# tweeq-Stamp_I2C_Temp_TMP102.net
KiCad netlist of a schematic drawn in EAGLE
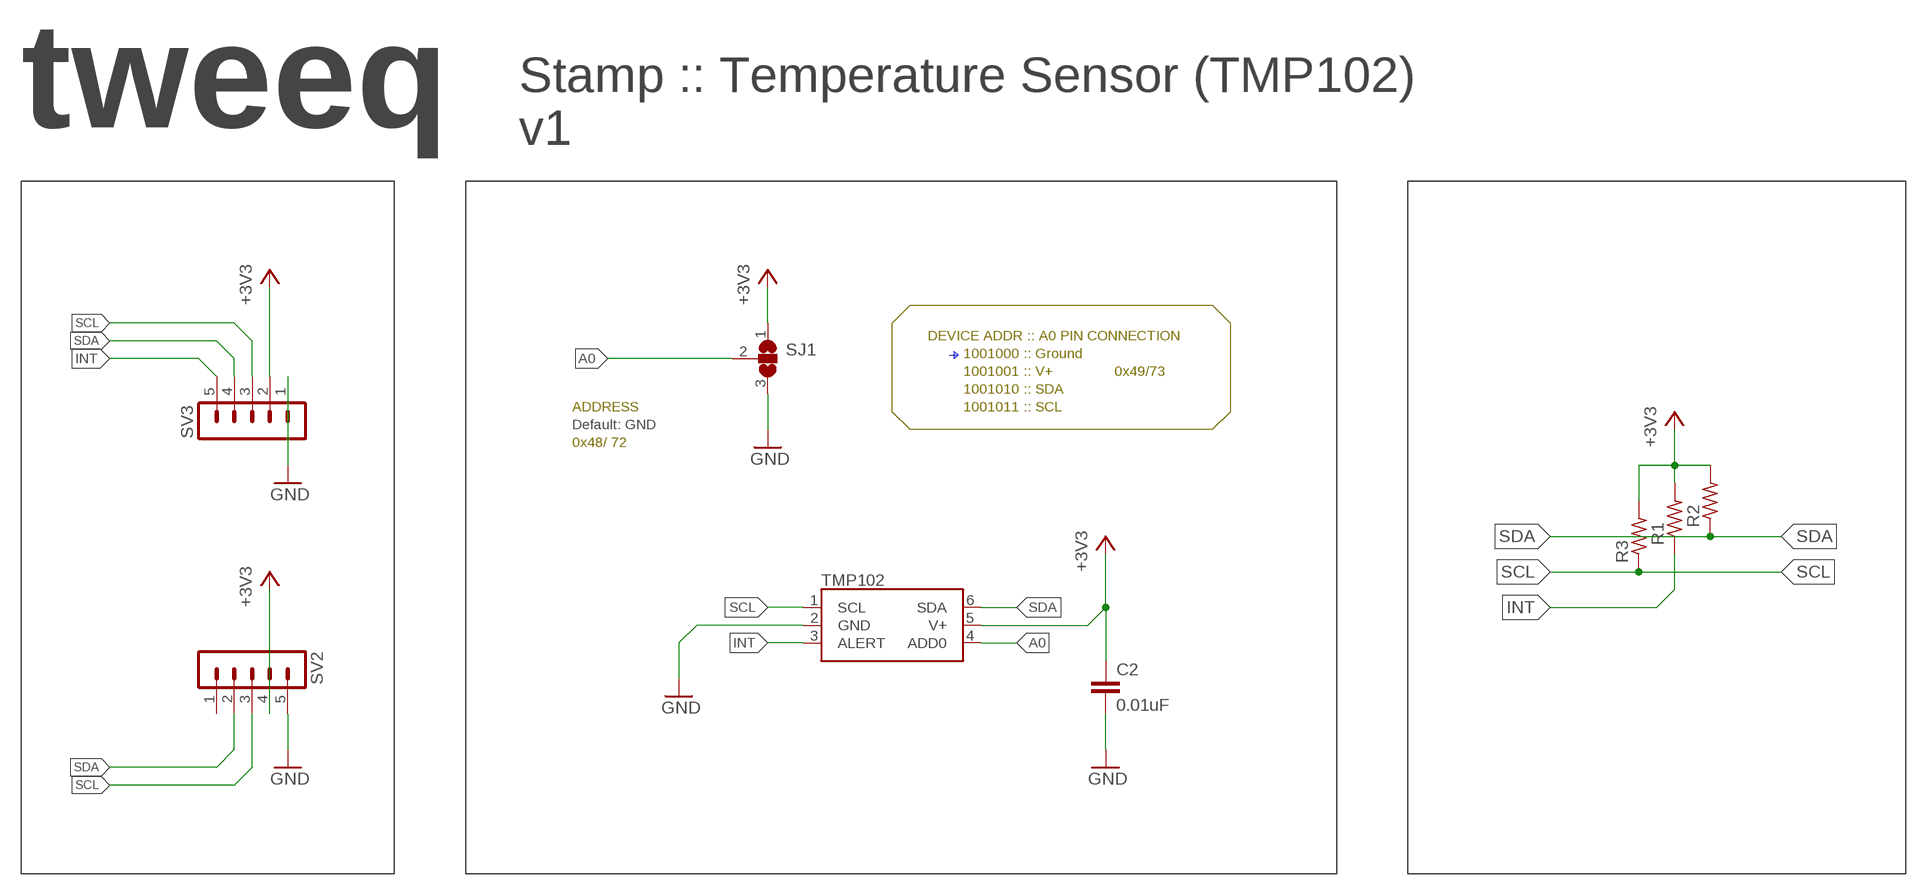
[diagram p0: schematic, sheet 1]

(export (version "E")
  (design (tool "Eeschema 10.0.6"))
  (components
    (comp (ref "C2")
      (value "0.01uF")
      (footprint "eagle-import:C0402K")
      (libsource (lib "eagle-import") (part "C-EUC0402K"))
    )
    (comp (ref "R1")
      (value "R-US_R0402")
      (footprint "eagle-import:R0402")
      (libsource (lib "eagle-import") (part "R-US_R0402"))
    )
    (comp (ref "R2")
      (value "R-US_R0402")
      (footprint "eagle-import:R0402")
      (libsource (lib "eagle-import") (part "R-US_R0402"))
    )
    (comp (ref "R3")
      (value "R-US_R0402")
      (footprint "eagle-import:R0402")
      (libsource (lib "eagle-import") (part "R-US_R0402"))
    )
    (comp (ref "SJ1")
      (value "JUMPER_SJ2WS")
      (footprint "eagle-import:JUMPER_SJ_S")
      (libsource (lib "eagle-import") (part "JUMPER_SJ2WS"))
    )
    (comp (ref "SV2")
      (value "M05-1STAMP")
      (footprint "eagle-import:1X05-1.5MM-STAMP")
      (libsource (lib "eagle-import") (part "M05-1STAMP"))
    )
    (comp (ref "SV3")
      (value "M05-1STAMP")
      (footprint "eagle-import:1X05-1.5MM-STAMP")
      (libsource (lib "eagle-import") (part "M05-1STAMP"))
    )
    (comp (ref "TMP102")
      (value "TMP102/SOT563")
      (footprint "eagle-import:SOT563")
      (libsource (lib "eagle-import") (part "TMP102/SOT563"))
    )
  )
  (nets
    (net (code "1") (name "+3V3") (class "Default")
      (node (ref "C2") (pin "1") (pinfunction "1_1") (pintype "passive"))
      (node (ref "R1") (pin "2") (pinfunction "2_2") (pintype "passive"))
      (node (ref "R2") (pin "2") (pinfunction "2_2") (pintype "passive"))
      (node (ref "R3") (pin "2") (pinfunction "2_2") (pintype "passive"))
      (node (ref "SJ1") (pin "1") (pinfunction "1_1") (pintype "passive"))
      (node (ref "SV2") (pin "4") (pinfunction "4_4") (pintype "passive"))
      (node (ref "SV3") (pin "2") (pinfunction "2_2") (pintype "passive"))
      (node (ref "TMP102") (pin "5") (pinfunction "V+_5") (pintype "bidirectional"))
    )
    (net (code "2") (name "A0") (class "Default")
      (node (ref "SJ1") (pin "2") (pinfunction "2_2") (pintype "passive"))
      (node (ref "TMP102") (pin "4") (pinfunction "ADD0_4") (pintype "bidirectional"))
    )
    (net (code "3") (name "GND") (class "Default")
      (node (ref "C2") (pin "2") (pinfunction "2_2") (pintype "passive"))
      (node (ref "SJ1") (pin "3") (pinfunction "3_3") (pintype "passive"))
      (node (ref "SV2") (pin "5") (pinfunction "5_5") (pintype "passive"))
      (node (ref "SV3") (pin "1") (pinfunction "1_1") (pintype "passive"))
      (node (ref "TMP102") (pin "2") (pinfunction "GND_2") (pintype "bidirectional"))
    )
    (net (code "4") (name "INT") (class "Default")
      (node (ref "R1") (pin "1") (pinfunction "1_1") (pintype "passive"))
      (node (ref "SV3") (pin "5") (pinfunction "5_5") (pintype "passive"))
      (node (ref "TMP102") (pin "3") (pinfunction "ALERT_3") (pintype "bidirectional"))
    )
    (net (code "5") (name "SCL") (class "Default")
      (node (ref "R3") (pin "1") (pinfunction "1_1") (pintype "passive"))
      (node (ref "SV2") (pin "3") (pinfunction "3_3") (pintype "passive"))
      (node (ref "SV3") (pin "3") (pinfunction "3_3") (pintype "passive"))
      (node (ref "TMP102") (pin "1") (pinfunction "SCL_1") (pintype "bidirectional"))
    )
    (net (code "6") (name "SDA") (class "Default")
      (node (ref "R2") (pin "1") (pinfunction "1_1") (pintype "passive"))
      (node (ref "SV2") (pin "2") (pinfunction "2_2") (pintype "passive"))
      (node (ref "SV3") (pin "4") (pinfunction "4_4") (pintype "passive"))
      (node (ref "TMP102") (pin "6") (pinfunction "SDA_6") (pintype "bidirectional"))
    )
    (net (code "7") (name "unconnected-(SV2-Pad1)") (class "Default")
      (node (ref "SV2") (pin "1") (pinfunction "1_1") (pintype "passive"))
    )
  )
)
